# Stage2_Amplifier.net
KiCad netlist of a schematic drawn in EAGLE
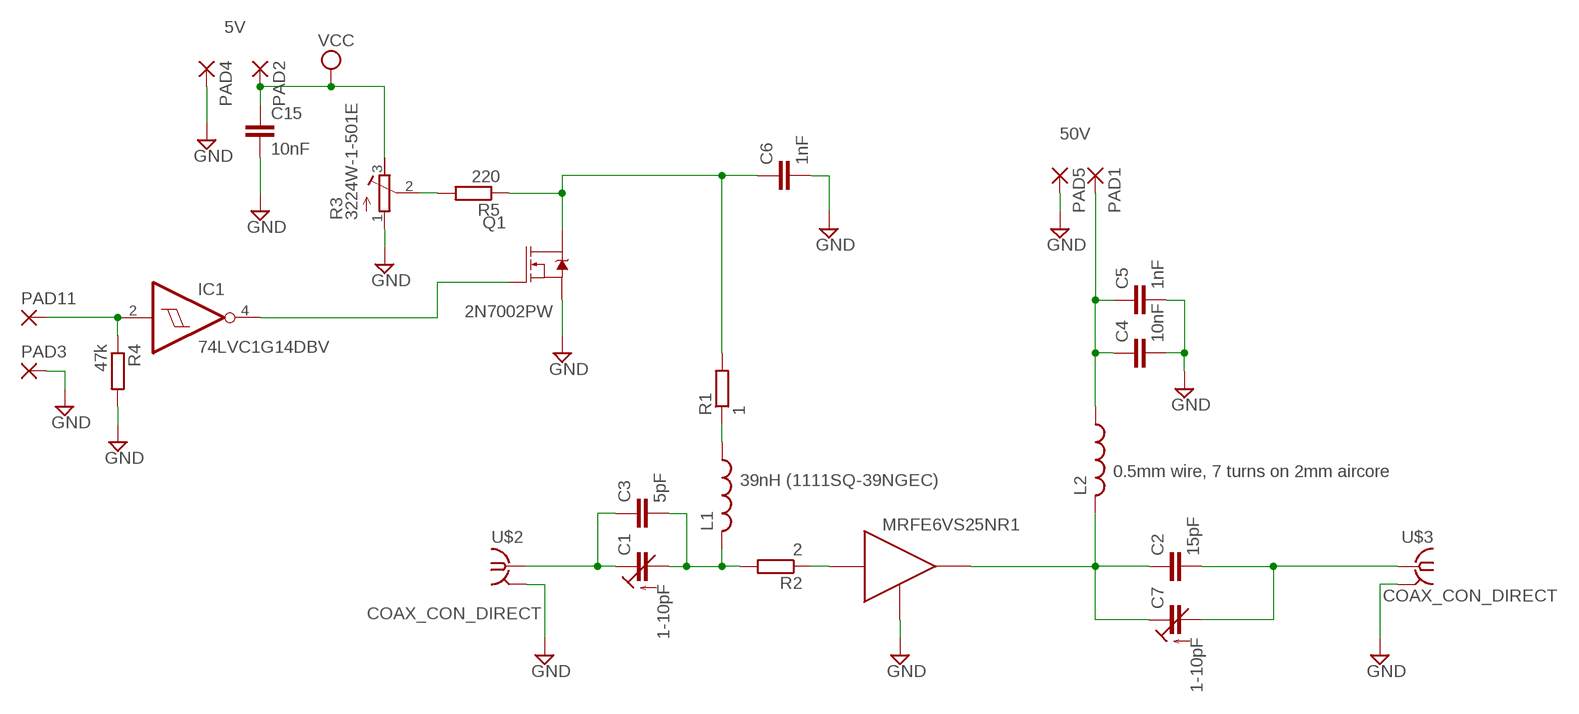
[diagram p0: schematic, sheet 1]

(export (version "E")
  (design (tool "Eeschema 10.0.6"))
  (components
    (comp (ref "C1")
      (value "1-10pF")
      (footprint "eagle-import:CTRIMTZBX4")
      (libsource (lib "eagle-import") (part "C-TRIMMTZBX4"))
    )
    (comp (ref "C2")
      (value "15pF")
      (footprint "eagle-import:C1210")
      (libsource (lib "eagle-import") (part "C-EUC1210"))
    )
    (comp (ref "C3")
      (value "5pF")
      (footprint "eagle-import:C1210")
      (libsource (lib "eagle-import") (part "C-EUC1210"))
    )
    (comp (ref "C4")
      (value "10nF")
      (footprint "eagle-import:C1206")
      (libsource (lib "eagle-import") (part "C-EUC1206"))
    )
    (comp (ref "C5")
      (value "1nF")
      (footprint "eagle-import:C1206")
      (libsource (lib "eagle-import") (part "C-EUC1206"))
    )
    (comp (ref "C6")
      (value "1nF")
      (footprint "eagle-import:C0805")
      (libsource (lib "eagle-import") (part "C-EUC0805"))
    )
    (comp (ref "C7")
      (value "1-10pF")
      (footprint "eagle-import:CTRIMTZBX4")
      (libsource (lib "eagle-import") (part "C-TRIMMTZBX4"))
    )
    (comp (ref "C15")
      (value "10nF")
      (footprint "eagle-import:C0805")
      (libsource (lib "eagle-import") (part "C-EUC0805"))
    )
    (comp (ref "IC1")
      (value "74LVC1G14DBV")
      (footprint "eagle-import:SOT23-5")
      (libsource (lib "eagle-import") (part "741G14DBVLVC"))
    )
    (comp (ref "L1")
      (value "39nH (1111SQ-39NGEC)")
      (footprint "eagle-import:L3225P")
      (libsource (lib "eagle-import") (part "L-USL3225P"))
    )
    (comp (ref "L2")
      (value "L-USL3225P")
      (footprint "eagle-import:L3225P")
      (libsource (lib "eagle-import") (part "L-USL3225P"))
    )
    (comp (ref "PAD1")
      (value "SMD5")
      (footprint "eagle-import:SMD2,54-5,08")
      (libsource (lib "eagle-import") (part "SMD5"))
    )
    (comp (ref "PAD2")
      (value "SMD5")
      (footprint "eagle-import:SMD2,54-5,08")
      (libsource (lib "eagle-import") (part "SMD5"))
    )
    (comp (ref "PAD3")
      (value "SMD5")
      (footprint "eagle-import:SMD2,54-5,08")
      (libsource (lib "eagle-import") (part "SMD5"))
    )
    (comp (ref "PAD4")
      (value "SMD5")
      (footprint "eagle-import:SMD2,54-5,08")
      (libsource (lib "eagle-import") (part "SMD5"))
    )
    (comp (ref "PAD5")
      (value "SMD5")
      (footprint "eagle-import:SMD2,54-5,08")
      (libsource (lib "eagle-import") (part "SMD5"))
    )
    (comp (ref "PAD11")
      (value "SMD5")
      (footprint "eagle-import:SMD2,54-5,08")
      (libsource (lib "eagle-import") (part "SMD5"))
    )
    (comp (ref "Q1")
      (value "2N7002PW")
      (footprint "eagle-import:SOT323")
      (libsource (lib "eagle-import") (part "MOSFET-NCH-2N7002PW"))
    )
    (comp (ref "R1")
      (value "1")
      (footprint "eagle-import:R1206")
      (libsource (lib "eagle-import") (part "R-EU_R1206"))
    )
    (comp (ref "R2")
      (value "2")
      (footprint "eagle-import:R1206")
      (libsource (lib "eagle-import") (part "R-EU_R1206"))
    )
    (comp (ref "R3")
      (value "3224W-1-501E")
      (footprint "eagle-import:RTRIM3224W")
      (libsource (lib "eagle-import") (part "R-TRIMM3224W"))
    )
    (comp (ref "R4")
      (value "47k")
      (footprint "eagle-import:R0805")
      (libsource (lib "eagle-import") (part "R-EU_R0805"))
    )
    (comp (ref "R5")
      (value "220")
      (footprint "eagle-import:R0805")
      (libsource (lib "eagle-import") (part "R-EU_R0805"))
    )
    (comp (ref "U$1")
      (value "MRFE6VS25NR1")
      (footprint "eagle-import:TO-270_ONBOARD")
      (libsource (lib "eagle-import") (part "AFT05MS031_BOARD"))
    )
    (comp (ref "U$2")
      (value "COAX_CON_DIRECT")
      (footprint "eagle-import:COAX.141")
      (libsource (lib "eagle-import") (part "COAX_CON_DIRECT"))
    )
    (comp (ref "U$3")
      (value "COAX_CON_DIRECT")
      (footprint "eagle-import:COAX.141")
      (libsource (lib "eagle-import") (part "COAX_CON_DIRECT"))
    )
  )
  (nets
    (net (code "1") (name "GND") (class "Default")
      (node (ref "C15") (pin "2") (pinfunction "2_2") (pintype "passive"))
      (node (ref "C4") (pin "2") (pinfunction "2_2") (pintype "passive"))
      (node (ref "C5") (pin "2") (pinfunction "2_2") (pintype "passive"))
      (node (ref "C6") (pin "2") (pinfunction "2_2") (pintype "passive"))
      (node (ref "PAD3") (pin "1") (pinfunction "P_1") (pintype "passive"))
      (node (ref "PAD4") (pin "1") (pinfunction "P_1") (pintype "passive"))
      (node (ref "PAD5") (pin "1") (pinfunction "P_1") (pintype "passive"))
      (node (ref "Q1") (pin "2") (pinfunction "S_2") (pintype "bidirectional"))
      (node (ref "R3") (pin "1") (pinfunction "A_1") (pintype "passive"))
      (node (ref "R4") (pin "2") (pinfunction "2_2") (pintype "passive"))
      (node (ref "U$1") (pin "P$3") (pinfunction "GND_P$3") (pintype "bidirectional"))
      (node (ref "U$2") (pin "P$2") (pinfunction "GND_P$2") (pintype "passive"))
      (node (ref "U$3") (pin "P$2") (pinfunction "GND_P$2") (pintype "passive"))
    )
    (net (code "2") (name "Net-(C1-A)") (class "Default")
      (node (ref "C1") (pin "2") (pinfunction "A_2") (pintype "passive"))
      (node (ref "C3") (pin "2") (pinfunction "2_2") (pintype "passive"))
      (node (ref "L1") (pin "2") (pinfunction "2_2") (pintype "passive"))
      (node (ref "R2") (pin "2") (pinfunction "2_2") (pintype "passive"))
    )
    (net (code "3") (name "Net-(C1-E)") (class "Default")
      (node (ref "C1") (pin "1") (pinfunction "E_1") (pintype "passive"))
      (node (ref "C3") (pin "1") (pinfunction "1_1") (pintype "passive"))
      (node (ref "U$2") (pin "P$1") (pinfunction "1_P$1") (pintype "passive"))
    )
    (net (code "4") (name "Net-(C7-A)") (class "Default")
      (node (ref "C2") (pin "2") (pinfunction "2_2") (pintype "passive"))
      (node (ref "C7") (pin "2") (pinfunction "A_2") (pintype "passive"))
      (node (ref "U$3") (pin "P$1") (pinfunction "1_P$1") (pintype "passive"))
    )
    (net (code "5") (name "Net-(C7-E)") (class "Default")
      (node (ref "C2") (pin "1") (pinfunction "1_1") (pintype "passive"))
      (node (ref "C7") (pin "1") (pinfunction "E_1") (pintype "passive"))
      (node (ref "L2") (pin "2") (pinfunction "2_2") (pintype "passive"))
      (node (ref "U$1") (pin "P$1") (pinfunction "OUT_P$1") (pintype "bidirectional"))
    )
    (net (code "6") (name "Net-(IC1A-I)") (class "Default")
      (node (ref "IC1") (pin "2") (pinfunction "I_2") (pintype "input"))
      (node (ref "PAD11") (pin "1") (pinfunction "P_1") (pintype "passive"))
      (node (ref "R4") (pin "1") (pinfunction "1_1") (pintype "passive"))
    )
    (net (code "7") (name "Net-(IC1A-O)") (class "Default")
      (node (ref "IC1") (pin "4") (pinfunction "O_4") (pintype "output"))
      (node (ref "Q1") (pin "1") (pinfunction "G_1") (pintype "bidirectional"))
    )
    (net (code "8") (name "Net-(L1-Pad1)") (class "Default")
      (node (ref "L1") (pin "1") (pinfunction "1_1") (pintype "passive"))
      (node (ref "R1") (pin "1") (pinfunction "1_1") (pintype "passive"))
    )
    (net (code "9") (name "Net-(PAD1-P)") (class "Default")
      (node (ref "C4") (pin "1") (pinfunction "1_1") (pintype "passive"))
      (node (ref "C5") (pin "1") (pinfunction "1_1") (pintype "passive"))
      (node (ref "L2") (pin "1") (pinfunction "1_1") (pintype "passive"))
      (node (ref "PAD1") (pin "1") (pinfunction "P_1") (pintype "passive"))
    )
    (net (code "10") (name "Net-(Q1-D)") (class "Default")
      (node (ref "C6") (pin "1") (pinfunction "1_1") (pintype "passive"))
      (node (ref "Q1") (pin "3") (pinfunction "D_3") (pintype "bidirectional"))
      (node (ref "R1") (pin "2") (pinfunction "2_2") (pintype "passive"))
      (node (ref "R5") (pin "1") (pinfunction "1_1") (pintype "passive"))
    )
    (net (code "11") (name "Net-(R3-S)") (class "Default")
      (node (ref "R3") (pin "2") (pinfunction "S_2") (pintype "passive"))
      (node (ref "R5") (pin "2") (pinfunction "2_2") (pintype "passive"))
    )
    (net (code "12") (name "Net-(U$1-IN)") (class "Default")
      (node (ref "R2") (pin "1") (pinfunction "1_1") (pintype "passive"))
      (node (ref "U$1") (pin "P$2") (pinfunction "IN_P$2") (pintype "bidirectional"))
    )
    (net (code "13") (name "VCC") (class "Default")
      (node (ref "C15") (pin "1") (pinfunction "1_1") (pintype "passive"))
      (node (ref "PAD2") (pin "1") (pinfunction "P_1") (pintype "passive"))
      (node (ref "R3") (pin "3") (pinfunction "E_3") (pintype "passive"))
    )
  )
)
